# FXIMU.net
KiCad netlist of a schematic drawn in EAGLE
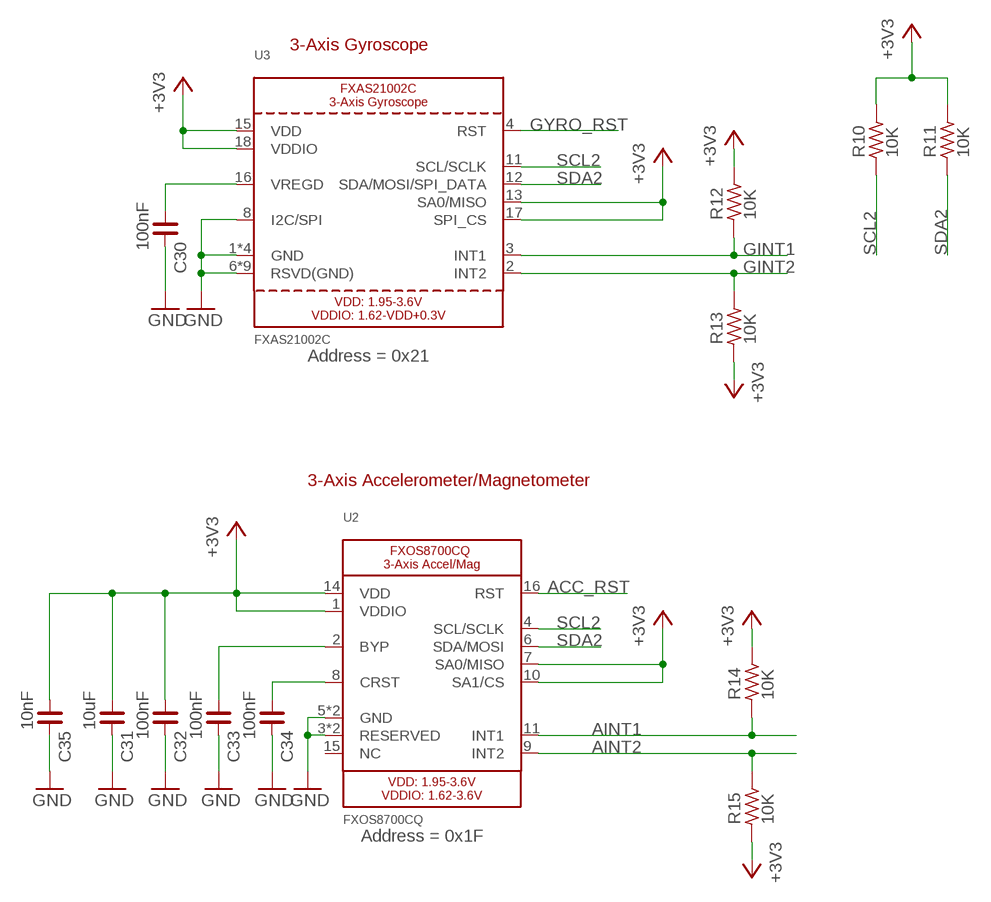
[diagram p0: schematic, sheet 1]
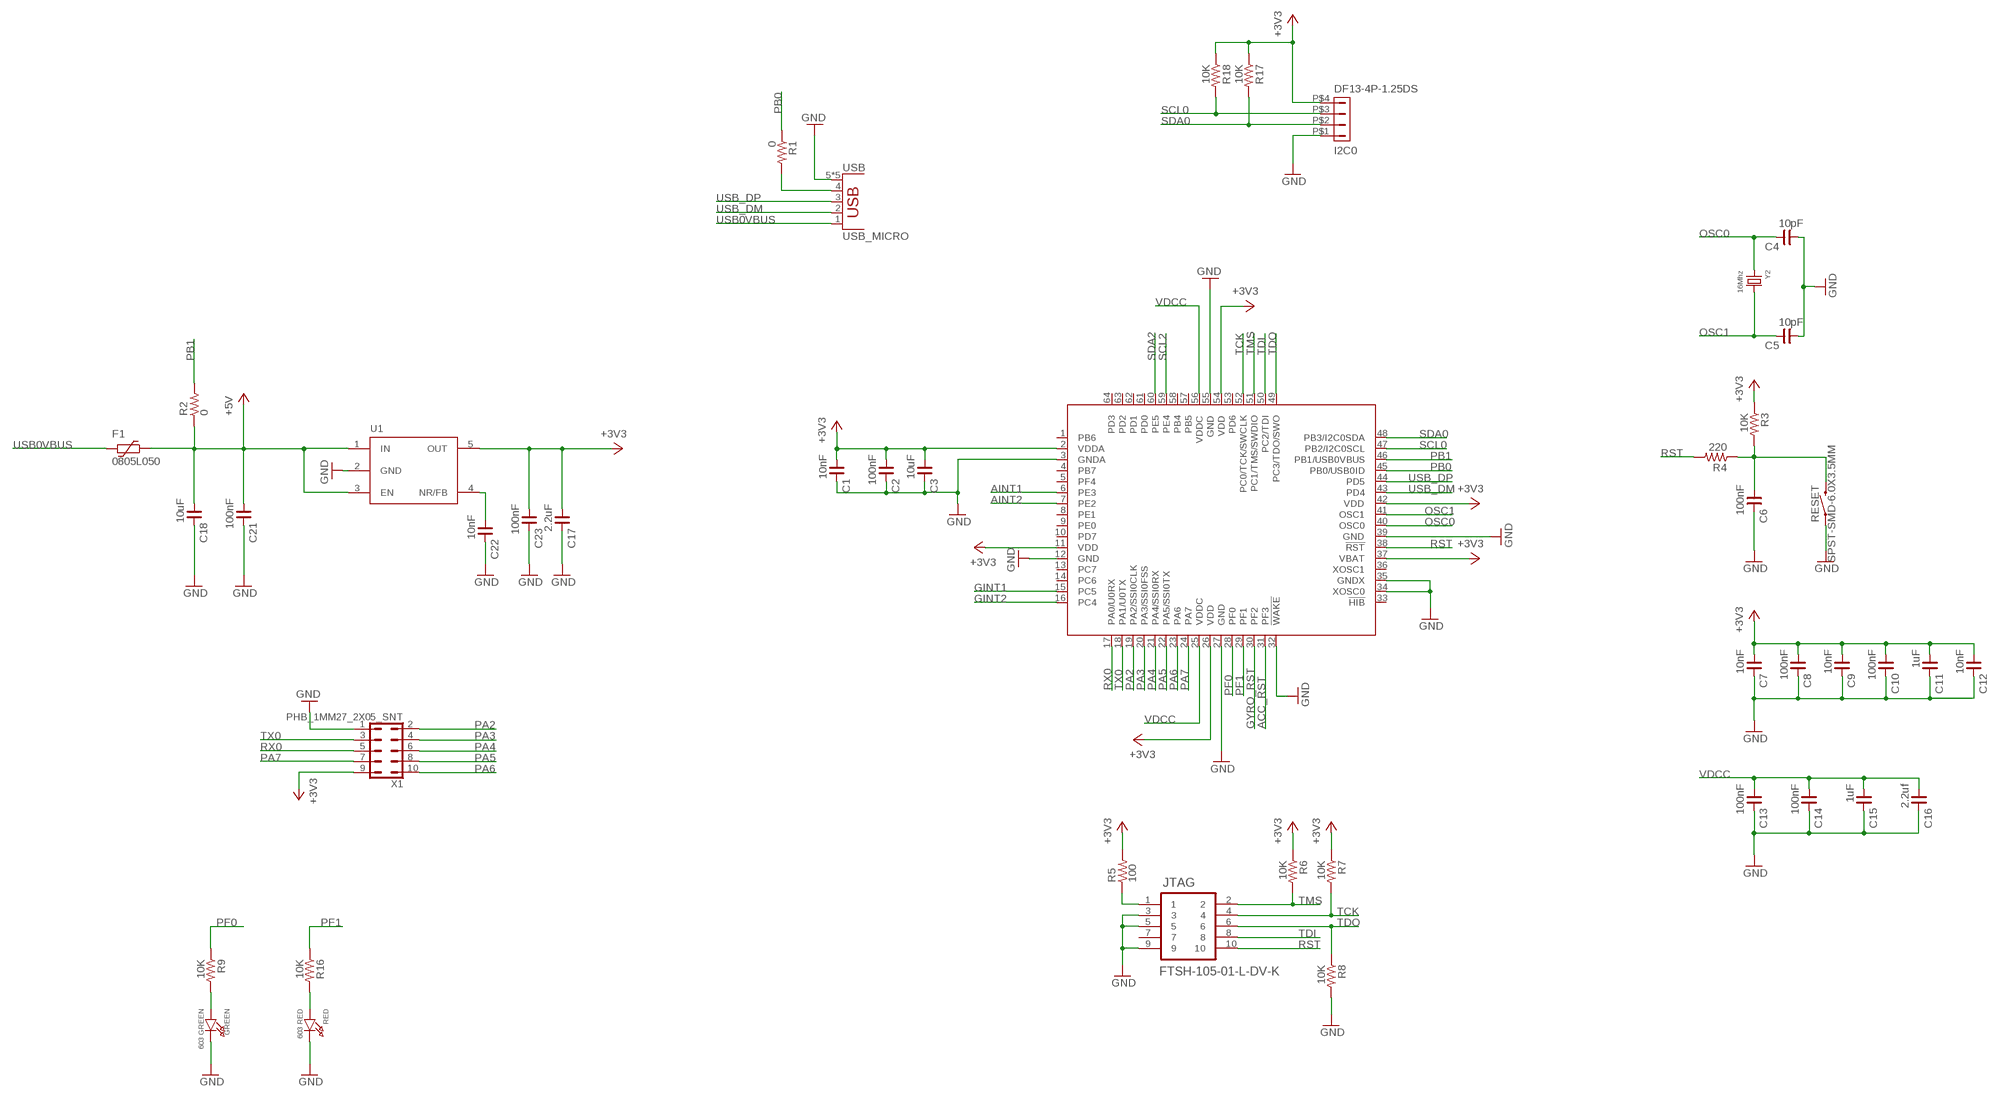
[diagram p1: schematic, sheet 2]

(export (version "E")
  (design (tool "Eeschema 10.0.6"))
  (components
    (comp (ref "C1")
      (value "10nF")
      (footprint "eagle-import:C0402")
      (libsource (lib "eagle-import") (part "C_0402"))
    )
    (comp (ref "C2")
      (value "100nF")
      (footprint "eagle-import:C0402")
      (libsource (lib "eagle-import") (part "C_0402"))
    )
    (comp (ref "C3")
      (value "10uF")
      (footprint "eagle-import:C0603")
      (libsource (lib "eagle-import") (part "C_0603"))
    )
    (comp (ref "C4")
      (value "10pF")
      (footprint "eagle-import:C0402")
      (libsource (lib "eagle-import") (part "C_0402"))
    )
    (comp (ref "C5")
      (value "10pF")
      (footprint "eagle-import:C0402")
      (libsource (lib "eagle-import") (part "C_0402"))
    )
    (comp (ref "C6")
      (value "100nF")
      (footprint "eagle-import:C0402")
      (libsource (lib "eagle-import") (part "C_0402"))
    )
    (comp (ref "C7")
      (value "10nF")
      (footprint "eagle-import:C0402")
      (libsource (lib "eagle-import") (part "C_0402"))
    )
    (comp (ref "C8")
      (value "100nF")
      (footprint "eagle-import:C0402")
      (libsource (lib "eagle-import") (part "C_0402"))
    )
    (comp (ref "C9")
      (value "10nF")
      (footprint "eagle-import:C0402")
      (libsource (lib "eagle-import") (part "C_0402"))
    )
    (comp (ref "C10")
      (value "100nF")
      (footprint "eagle-import:C0402")
      (libsource (lib "eagle-import") (part "C_0402"))
    )
    (comp (ref "C11")
      (value "1uF")
      (footprint "eagle-import:C0402")
      (libsource (lib "eagle-import") (part "C_0402"))
    )
    (comp (ref "C12")
      (value "10nF")
      (footprint "eagle-import:C0402")
      (libsource (lib "eagle-import") (part "C_0402"))
    )
    (comp (ref "C13")
      (value "100nF")
      (footprint "eagle-import:C0402")
      (libsource (lib "eagle-import") (part "C_0402"))
    )
    (comp (ref "C14")
      (value "100nF")
      (footprint "eagle-import:C0402")
      (libsource (lib "eagle-import") (part "C_0402"))
    )
    (comp (ref "C15")
      (value "1uF")
      (footprint "eagle-import:C0402")
      (libsource (lib "eagle-import") (part "C_0402"))
    )
    (comp (ref "C16")
      (value "2.2uf")
      (footprint "eagle-import:C0603")
      (libsource (lib "eagle-import") (part "C_0603"))
    )
    (comp (ref "C17")
      (value "2.2uF")
      (footprint "eagle-import:C0603")
      (libsource (lib "eagle-import") (part "C_0603"))
    )
    (comp (ref "C18")
      (value "10uF")
      (footprint "eagle-import:C0603")
      (libsource (lib "eagle-import") (part "C_0603"))
    )
    (comp (ref "C21")
      (value "100nF")
      (footprint "eagle-import:C0402")
      (libsource (lib "eagle-import") (part "C_0402"))
    )
    (comp (ref "C22")
      (value "10nF")
      (footprint "eagle-import:C0402")
      (libsource (lib "eagle-import") (part "C_0402"))
    )
    (comp (ref "C23")
      (value "100nF")
      (footprint "eagle-import:C0402")
      (libsource (lib "eagle-import") (part "C_0402"))
    )
    (comp (ref "F1")
      (value "0805L050")
      (footprint "eagle-import:0805L")
      (fields (field (name "MF") "Littelfuse"))
      (libsource (lib "eagle-import") (part "?0805L050"))
    )
    (comp (ref "GREEN")
      (value "603 GREEN")
      (footprint "eagle-import:CHIPLED_0603")
      (libsource (lib "eagle-import") (part "LED0603"))
    )
    (comp (ref "I2C0")
      (value "DF13-4P-1.25DS")
      (footprint "eagle-import:DF13-4P-1.25DS")
      (libsource (lib "eagle-import") (part "DF13-4P-1.25DS"))
    )
    (comp (ref "IC1")
      (value "TM4C123[7,G]XXPM")
      (footprint "eagle-import:PM_S-PQFP-G64")
      (libsource (lib "eagle-import") (part "TM4C123[7,G]XXPM"))
    )
    (comp (ref "JTAG")
      (value "FTSH-105-01-L-DV-K")
      (footprint "eagle-import:SAMTEC_FTSH-105-01-L-DV-K")
      (fields (field (name "MF") "Samtec"))
      (libsource (lib "eagle-import") (part "FTSH-105-01-L-DV-K"))
    )
    (comp (ref "R1")
      (value "0")
      (footprint "eagle-import:R0402")
      (libsource (lib "eagle-import") (part "R_0402"))
    )
    (comp (ref "R2")
      (value "0")
      (footprint "eagle-import:R0402")
      (libsource (lib "eagle-import") (part "R_0402"))
    )
    (comp (ref "R3")
      (value "10K")
      (footprint "eagle-import:R0402")
      (libsource (lib "eagle-import") (part "R_0402"))
    )
    (comp (ref "R4")
      (value "220")
      (footprint "eagle-import:R0402")
      (libsource (lib "eagle-import") (part "R_0402"))
    )
    (comp (ref "R5")
      (value "100")
      (footprint "eagle-import:R0402")
      (libsource (lib "eagle-import") (part "R_0402"))
    )
    (comp (ref "R6")
      (value "10K")
      (footprint "eagle-import:R0402")
      (libsource (lib "eagle-import") (part "R_0402"))
    )
    (comp (ref "R7")
      (value "10K")
      (footprint "eagle-import:R0402")
      (libsource (lib "eagle-import") (part "R_0402"))
    )
    (comp (ref "R8")
      (value "10K")
      (footprint "eagle-import:R0402")
      (libsource (lib "eagle-import") (part "R_0402"))
    )
    (comp (ref "R9")
      (value "10K")
      (footprint "eagle-import:R0402")
      (libsource (lib "eagle-import") (part "R_0402"))
    )
    (comp (ref "R16")
      (value "10K")
      (footprint "eagle-import:R0402")
      (libsource (lib "eagle-import") (part "R_0402"))
    )
    (comp (ref "R17")
      (value "10K")
      (footprint "eagle-import:R0402")
      (libsource (lib "eagle-import") (part "R_0402"))
    )
    (comp (ref "R18")
      (value "10K")
      (footprint "eagle-import:R0402")
      (libsource (lib "eagle-import") (part "R_0402"))
    )
    (comp (ref "RED")
      (value "603 RED")
      (footprint "eagle-import:CHIPLED_0603")
      (libsource (lib "eagle-import") (part "LED0603"))
    )
    (comp (ref "RESET")
      (value "SPST-SMD-6.0X3.5MM")
      (footprint "eagle-import:TACTILE_SWITCH_SMD_6.0X3.5MM")
      (libsource (lib "eagle-import") (part "MOMENTARY-SWITCH-SPST-SMD-6.0X3.5MM"))
    )
    (comp (ref "U1")
      (value "TPS73633")
      (footprint "eagle-import:SOT23-5L")
      (libsource (lib "eagle-import") (part "TPS73633"))
    )
    (comp (ref "USB")
      (value "USB_MICRO")
      (footprint "eagle-import:USB_MICRO_MOLEX_FULL")
      (libsource (lib "eagle-import") (part "USB_MICRO"))
    )
    (comp (ref "X1")
      (value "PHB_1MM27_2X05_SNT")
      (footprint "eagle-import:PHB_1MM27_2X05_SNT")
      (libsource (lib "eagle-import") (part "PHB_1MM27_2X05_SNT"))
    )
    (comp (ref "Y2")
      (value "16Mhz")
      (footprint "eagle-import:6X3.3MM")
      (libsource (lib "eagle-import") (part "CRYSTAL.6X3.3MM"))
    )
    (comp (ref "C30")
      (value "100nF")
      (footprint "eagle-import:C0402")
      (libsource (lib "eagle-import") (part "C_0402"))
    )
    (comp (ref "C31")
      (value "10uF")
      (footprint "eagle-import:C0603")
      (libsource (lib "eagle-import") (part "C_0603"))
    )
    (comp (ref "C32")
      (value "100nF")
      (footprint "eagle-import:C0402")
      (libsource (lib "eagle-import") (part "C_0402"))
    )
    (comp (ref "C33")
      (value "100nF")
      (footprint "eagle-import:C0402")
      (libsource (lib "eagle-import") (part "C_0402"))
    )
    (comp (ref "C34")
      (value "100nF")
      (footprint "eagle-import:C0402")
      (libsource (lib "eagle-import") (part "C_0402"))
    )
    (comp (ref "C35")
      (value "10nF")
      (footprint "eagle-import:C0402")
      (libsource (lib "eagle-import") (part "C_0402"))
    )
    (comp (ref "R10")
      (value "10K")
      (footprint "eagle-import:R0402")
      (libsource (lib "eagle-import") (part "R_0402"))
    )
    (comp (ref "R11")
      (value "10K")
      (footprint "eagle-import:R0402")
      (libsource (lib "eagle-import") (part "R_0402"))
    )
    (comp (ref "R12")
      (value "10K")
      (footprint "eagle-import:R0402")
      (libsource (lib "eagle-import") (part "R_0402"))
    )
    (comp (ref "R13")
      (value "10K")
      (footprint "eagle-import:R0402")
      (libsource (lib "eagle-import") (part "R_0402"))
    )
    (comp (ref "R14")
      (value "10K")
      (footprint "eagle-import:R0402")
      (libsource (lib "eagle-import") (part "R_0402"))
    )
    (comp (ref "R15")
      (value "10K")
      (footprint "eagle-import:R0402")
      (libsource (lib "eagle-import") (part "R_0402"))
    )
    (comp (ref "U2")
      (value "FXOS8700CQ")
      (footprint "eagle-import:QFN16_3MM_FREESCALE_5X3")
      (libsource (lib "eagle-import") (part "ACCEL_MAG_FXOS8700CQ"))
    )
    (comp (ref "U3")
      (value "FXAS21002C")
      (footprint "eagle-import:QFN24_4MM_FREESCALE_7X5")
      (libsource (lib "eagle-import") (part "GYRO_FXAS21002C"))
    )
  )
  (nets
    (net (code "1") (name "+3V3") (class "Default")
      (node (ref "C1") (pin "1") (pinfunction "1_1") (pintype "passive"))
      (node (ref "C10") (pin "1") (pinfunction "1_1") (pintype "passive"))
      (node (ref "C11") (pin "1") (pinfunction "1_1") (pintype "passive"))
      (node (ref "C12") (pin "1") (pinfunction "1_1") (pintype "passive"))
      (node (ref "C17") (pin "1") (pinfunction "1_1") (pintype "passive"))
      (node (ref "C2") (pin "1") (pinfunction "1_1") (pintype "passive"))
      (node (ref "C23") (pin "1") (pinfunction "1_1") (pintype "passive"))
      (node (ref "C3") (pin "1") (pinfunction "1_1") (pintype "passive"))
      (node (ref "C31") (pin "1") (pinfunction "1_1") (pintype "passive"))
      (node (ref "C32") (pin "1") (pinfunction "1_1") (pintype "passive"))
      (node (ref "C35") (pin "1") (pinfunction "1_1") (pintype "passive"))
      (node (ref "C7") (pin "1") (pinfunction "1_1") (pintype "passive"))
      (node (ref "C8") (pin "1") (pinfunction "1_1") (pintype "passive"))
      (node (ref "C9") (pin "1") (pinfunction "1_1") (pintype "passive"))
      (node (ref "I2C0") (pin "P$4") (pinfunction "4_P$4") (pintype "passive"))
      (node (ref "IC1") (pin "11") (pinfunction "VDD_11") (pintype "bidirectional"))
      (node (ref "IC1") (pin "2") (pinfunction "VDDA_2") (pintype "bidirectional"))
      (node (ref "IC1") (pin "26") (pinfunction "VDD_26") (pintype "bidirectional"))
      (node (ref "IC1") (pin "37") (pinfunction "VBAT_37") (pintype "bidirectional"))
      (node (ref "IC1") (pin "42") (pinfunction "VDD_42") (pintype "bidirectional"))
      (node (ref "IC1") (pin "54") (pinfunction "VDD_54") (pintype "bidirectional"))
      (node (ref "R10") (pin "2") (pinfunction "2_2") (pintype "passive"))
      (node (ref "R11") (pin "2") (pinfunction "2_2") (pintype "passive"))
      (node (ref "R12") (pin "2") (pinfunction "2_2") (pintype "passive"))
      (node (ref "R13") (pin "1") (pinfunction "1_1") (pintype "passive"))
      (node (ref "R14") (pin "2") (pinfunction "2_2") (pintype "passive"))
      (node (ref "R15") (pin "1") (pinfunction "1_1") (pintype "passive"))
      (node (ref "R17") (pin "1") (pinfunction "1_1") (pintype "passive"))
      (node (ref "R18") (pin "1") (pinfunction "1_1") (pintype "passive"))
      (node (ref "R3") (pin "1") (pinfunction "1_1") (pintype "passive"))
      (node (ref "R5") (pin "2") (pinfunction "2_2") (pintype "passive"))
      (node (ref "R6") (pin "1") (pinfunction "1_1") (pintype "passive"))
      (node (ref "R7") (pin "1") (pinfunction "1_1") (pintype "passive"))
      (node (ref "U1") (pin "5") (pinfunction "OUT_5") (pintype "bidirectional"))
      (node (ref "U2") (pin "1") (pinfunction "VDDIO_1") (pintype "bidirectional"))
      (node (ref "U2") (pin "10") (pinfunction "SA1/CS_10") (pintype "bidirectional"))
      (node (ref "U2") (pin "14") (pinfunction "VDD_14") (pintype "bidirectional"))
      (node (ref "U2") (pin "7") (pinfunction "SA0/MISO_7") (pintype "bidirectional"))
      (node (ref "U3") (pin "13") (pinfunction "SA0/MISO_13") (pintype "bidirectional"))
      (node (ref "U3") (pin "15") (pinfunction "VDD_15") (pintype "bidirectional"))
      (node (ref "U3") (pin "17") (pinfunction "SPI_CS_17") (pintype "bidirectional"))
      (node (ref "U3") (pin "18") (pinfunction "VDDIO_18") (pintype "bidirectional"))
      (node (ref "X1") (pin "9") (pinfunction "9_9") (pintype "passive"))
    )
    (net (code "2") (name "+5V") (class "Default")
      (node (ref "C18") (pin "1") (pinfunction "1_1") (pintype "passive"))
      (node (ref "C21") (pin "1") (pinfunction "1_1") (pintype "passive"))
      (node (ref "F1") (pin "1") (pinfunction "1_1") (pintype "passive"))
      (node (ref "R2") (pin "1") (pinfunction "1_1") (pintype "passive"))
      (node (ref "U1") (pin "1") (pinfunction "IN_1") (pintype "bidirectional"))
      (node (ref "U1") (pin "3") (pinfunction "EN_3") (pintype "bidirectional"))
    )
    (net (code "3") (name "ACC_RST") (class "Default")
      (node (ref "IC1") (pin "31") (pinfunction "PF3_31") (pintype "bidirectional"))
      (node (ref "U2") (pin "16") (pinfunction "RST_16") (pintype "bidirectional"))
    )
    (net (code "4") (name "AINT1") (class "Default")
      (node (ref "IC1") (pin "6") (pinfunction "PE3_6") (pintype "bidirectional"))
      (node (ref "R14") (pin "1") (pinfunction "1_1") (pintype "passive"))
      (node (ref "U2") (pin "11") (pinfunction "INT1_11") (pintype "bidirectional"))
    )
    (net (code "5") (name "AINT2") (class "Default")
      (node (ref "IC1") (pin "7") (pinfunction "PE2_7") (pintype "bidirectional"))
      (node (ref "R15") (pin "2") (pinfunction "2_2") (pintype "passive"))
      (node (ref "U2") (pin "9") (pinfunction "INT2_9") (pintype "bidirectional"))
    )
    (net (code "6") (name "GINT1") (class "Default")
      (node (ref "IC1") (pin "15") (pinfunction "PC5_15") (pintype "bidirectional"))
      (node (ref "R12") (pin "1") (pinfunction "1_1") (pintype "passive"))
      (node (ref "U3") (pin "3") (pinfunction "INT1_3") (pintype "bidirectional"))
    )
    (net (code "7") (name "GINT2") (class "Default")
      (node (ref "IC1") (pin "16") (pinfunction "PC4_16") (pintype "bidirectional"))
      (node (ref "R13") (pin "2") (pinfunction "2_2") (pintype "passive"))
      (node (ref "U3") (pin "2") (pinfunction "INT2_2") (pintype "bidirectional"))
    )
    (net (code "8") (name "GND") (class "Default")
      (node (ref "C1") (pin "2") (pinfunction "2_2") (pintype "passive"))
      (node (ref "C10") (pin "2") (pinfunction "2_2") (pintype "passive"))
      (node (ref "C11") (pin "2") (pinfunction "2_2") (pintype "passive"))
      (node (ref "C12") (pin "2") (pinfunction "2_2") (pintype "passive"))
      (node (ref "C13") (pin "2") (pinfunction "2_2") (pintype "passive"))
      (node (ref "C14") (pin "2") (pinfunction "2_2") (pintype "passive"))
      (node (ref "C15") (pin "2") (pinfunction "2_2") (pintype "passive"))
      (node (ref "C16") (pin "2") (pinfunction "2_2") (pintype "passive"))
      (node (ref "C17") (pin "2") (pinfunction "2_2") (pintype "passive"))
      (node (ref "C18") (pin "2") (pinfunction "2_2") (pintype "passive"))
      (node (ref "C2") (pin "2") (pinfunction "2_2") (pintype "passive"))
      (node (ref "C21") (pin "2") (pinfunction "2_2") (pintype "passive"))
      (node (ref "C22") (pin "2") (pinfunction "2_2") (pintype "passive"))
      (node (ref "C23") (pin "2") (pinfunction "2_2") (pintype "passive"))
      (node (ref "C3") (pin "2") (pinfunction "2_2") (pintype "passive"))
      (node (ref "C30") (pin "2") (pinfunction "2_2") (pintype "passive"))
      (node (ref "C31") (pin "2") (pinfunction "2_2") (pintype "passive"))
      (node (ref "C32") (pin "2") (pinfunction "2_2") (pintype "passive"))
      (node (ref "C33") (pin "2") (pinfunction "2_2") (pintype "passive"))
      (node (ref "C34") (pin "2") (pinfunction "2_2") (pintype "passive"))
      (node (ref "C35") (pin "2") (pinfunction "2_2") (pintype "passive"))
      (node (ref "C4") (pin "1") (pinfunction "1_1") (pintype "passive"))
      (node (ref "C5") (pin "1") (pinfunction "1_1") (pintype "passive"))
      (node (ref "C6") (pin "2") (pinfunction "2_2") (pintype "passive"))
      (node (ref "C7") (pin "2") (pinfunction "2_2") (pintype "passive"))
      (node (ref "C8") (pin "2") (pinfunction "2_2") (pintype "passive"))
      (node (ref "C9") (pin "2") (pinfunction "2_2") (pintype "passive"))
      (node (ref "GREEN") (pin "C") (pinfunction "C_C") (pintype "passive"))
      (node (ref "I2C0") (pin "P$1") (pinfunction "1_P$1") (pintype "passive"))
      (node (ref "IC1") (pin "12") (pinfunction "GND_12") (pintype "bidirectional"))
      (node (ref "IC1") (pin "27") (pinfunction "GND_27") (pintype "bidirectional"))
      (node (ref "IC1") (pin "3") (pinfunction "GNDA_3") (pintype "bidirectional"))
      (node (ref "IC1") (pin "32") (pinfunction "~{WAKE}_32") (pintype "bidirectional"))
      (node (ref "IC1") (pin "34") (pinfunction "XOSC0_34") (pintype "bidirectional"))
      (node (ref "IC1") (pin "35") (pinfunction "GNDX_35") (pintype "bidirectional"))
      (node (ref "IC1") (pin "39") (pinfunction "GND_39") (pintype "bidirectional"))
      (node (ref "IC1") (pin "55") (pinfunction "GND_55") (pintype "bidirectional"))
      (node (ref "JTAG") (pin "3") (pinfunction "3_3") (pintype "passive"))
      (node (ref "JTAG") (pin "5") (pinfunction "5_5") (pintype "passive"))
      (node (ref "JTAG") (pin "9") (pinfunction "9_9") (pintype "passive"))
      (node (ref "R8") (pin "2") (pinfunction "2_2") (pintype "passive"))
      (node (ref "RED") (pin "C") (pinfunction "C_C") (pintype "passive"))
      (node (ref "RESET") (pin "1") (pinfunction "1_1") (pintype "passive"))
      (node (ref "U1") (pin "2") (pinfunction "GND_2") (pintype "bidirectional"))
      (node (ref "U2") (pin "12") (pinfunction "GND_12") (pintype "bidirectional"))
      (node (ref "U2") (pin "13") (pinfunction "RESERVED_13") (pintype "bidirectional"))
      (node (ref "U2") (pin "3") (pinfunction "RESERVED_3") (pintype "bidirectional"))
      (node (ref "U2") (pin "5") (pinfunction "GND_5") (pintype "bidirectional"))
      (node (ref "U3") (pin "1") (pinfunction "GND_1") (pintype "bidirectional"))
      (node (ref "U3") (pin "10") (pinfunction "RSVD(GND)_10") (pintype "bidirectional"))
      (node (ref "U3") (pin "14") (pinfunction "GND_14") (pintype "bidirectional"))
      (node (ref "U3") (pin "19") (pinfunction "GND_19") (pintype "bidirectional"))
      (node (ref "U3") (pin "20") (pinfunction "RSVD(GND)_20") (pintype "bidirectional"))
      (node (ref "U3") (pin "21") (pinfunction "RSVD(GND)_21") (pintype "bidirectional"))
      (node (ref "U3") (pin "22") (pinfunction "RSVD(GND)_22") (pintype "bidirectional"))
      (node (ref "U3") (pin "23") (pinfunction "RSVD(GND)_23") (pintype "bidirectional"))
      (node (ref "U3") (pin "24") (pinfunction "RSVD(GND)_24") (pintype "bidirectional"))
      (node (ref "U3") (pin "5") (pinfunction "GND_5") (pintype "bidirectional"))
      (node (ref "U3") (pin "6") (pinfunction "RSVD(GND)_6") (pintype "bidirectional"))
      (node (ref "U3") (pin "7") (pinfunction "RSVD(GND)_7") (pintype "bidirectional"))
      (node (ref "U3") (pin "8") (pinfunction "I2C/SPI_8") (pintype "bidirectional"))
      (node (ref "U3") (pin "9") (pinfunction "RSVD(GND)_9") (pintype "bidirectional"))
      (node (ref "USB") (pin "5") (pinfunction "GND_5") (pintype "bidirectional"))
      (node (ref "USB") (pin "P$1") (pinfunction "GND_P$1") (pintype "bidirectional"))
      (node (ref "USB") (pin "P$2") (pinfunction "GND_P$2") (pintype "bidirectional"))
      (node (ref "USB") (pin "P$3") (pinfunction "GND_P$3") (pintype "bidirectional"))
      (node (ref "USB") (pin "P$4") (pinfunction "GND_P$4") (pintype "bidirectional"))
      (node (ref "X1") (pin "1") (pinfunction "1_1") (pintype "passive"))
    )
    (net (code "9") (name "GYRO_RST") (class "Default")
      (node (ref "IC1") (pin "30") (pinfunction "PF2_30") (pintype "bidirectional"))
      (node (ref "U3") (pin "4") (pinfunction "RST_4") (pintype "bidirectional"))
    )
    (net (code "10") (name "Net-(C6-Pad1)") (class "Default")
      (node (ref "C6") (pin "1") (pinfunction "1_1") (pintype "passive"))
      (node (ref "R3") (pin "2") (pinfunction "2_2") (pintype "passive"))
      (node (ref "R4") (pin "1") (pinfunction "1_1") (pintype "passive"))
      (node (ref "RESET") (pin "2") (pinfunction "2_2") (pintype "passive"))
    )
    (net (code "11") (name "Net-(GREEN-PadA)") (class "Default")
      (node (ref "GREEN") (pin "A") (pinfunction "A_A") (pintype "passive"))
      (node (ref "R9") (pin "2") (pinfunction "2_2") (pintype "passive"))
    )
    (net (code "12") (name "Net-(JTAG-Pad1)") (class "Default")
      (node (ref "JTAG") (pin "1") (pinfunction "1_1") (pintype "passive"))
      (node (ref "R5") (pin "1") (pinfunction "1_1") (pintype "passive"))
    )
    (net (code "13") (name "Net-(R16-Pad2)") (class "Default")
      (node (ref "R16") (pin "2") (pinfunction "2_2") (pintype "passive"))
      (node (ref "RED") (pin "A") (pinfunction "A_A") (pintype "passive"))
    )
    (net (code "14") (name "Net-(U1-NR{slash}FB)") (class "Default")
      (node (ref "C22") (pin "1") (pinfunction "1_1") (pintype "passive"))
      (node (ref "U1") (pin "4") (pinfunction "NR/FB_4") (pintype "bidirectional"))
    )
    (net (code "15") (name "Net-(U2-BYP)") (class "Default")
      (node (ref "C33") (pin "1") (pinfunction "1_1") (pintype "passive"))
      (node (ref "U2") (pin "2") (pinfunction "BYP_2") (pintype "bidirectional"))
    )
    (net (code "16") (name "Net-(U2-CRST)") (class "Default")
      (node (ref "C34") (pin "1") (pinfunction "1_1") (pintype "passive"))
      (node (ref "U2") (pin "8") (pinfunction "CRST_8") (pintype "bidirectional"))
    )
    (net (code "17") (name "Net-(U3-VREGD)") (class "Default")
      (node (ref "C30") (pin "1") (pinfunction "1_1") (pintype "passive"))
      (node (ref "U3") (pin "16") (pinfunction "VREGD_16") (pintype "bidirectional"))
    )
    (net (code "18") (name "Net-(USB-ID)") (class "Default")
      (node (ref "R1") (pin "2") (pinfunction "2_2") (pintype "passive"))
      (node (ref "USB") (pin "4") (pinfunction "ID_4") (pintype "bidirectional"))
    )
    (net (code "19") (name "OSC0") (class "Default")
      (node (ref "C4") (pin "2") (pinfunction "2_2") (pintype "passive"))
      (node (ref "IC1") (pin "40") (pinfunction "OSC0_40") (pintype "bidirectional"))
      (node (ref "Y2") (pin "1") (pinfunction "1_1") (pintype "passive"))
    )
    (net (code "20") (name "OSC1") (class "Default")
      (node (ref "C5") (pin "2") (pinfunction "2_2") (pintype "passive"))
      (node (ref "IC1") (pin "41") (pinfunction "OSC1_41") (pintype "bidirectional"))
      (node (ref "Y2") (pin "2") (pinfunction "2_2") (pintype "passive"))
    )
    (net (code "21") (name "PA2") (class "Default")
      (node (ref "IC1") (pin "19") (pinfunction "PA2/SSI0CLK_19") (pintype "bidirectional"))
      (node (ref "X1") (pin "2") (pinfunction "2_2") (pintype "passive"))
    )
    (net (code "22") (name "PA3") (class "Default")
      (node (ref "IC1") (pin "20") (pinfunction "PA3/SSI0FSS_20") (pintype "bidirectional"))
      (node (ref "X1") (pin "4") (pinfunction "4_4") (pintype "passive"))
    )
    (net (code "23") (name "PA4") (class "Default")
      (node (ref "IC1") (pin "21") (pinfunction "PA4/SSI0RX_21") (pintype "bidirectional"))
      (node (ref "X1") (pin "6") (pinfunction "6_6") (pintype "passive"))
    )
    (net (code "24") (name "PA5") (class "Default")
      (node (ref "IC1") (pin "22") (pinfunction "PA5/SSI0TX_22") (pintype "bidirectional"))
      (node (ref "X1") (pin "8") (pinfunction "8_8") (pintype "passive"))
    )
    (net (code "25") (name "PA6") (class "Default")
      (node (ref "IC1") (pin "23") (pinfunction "PA6_23") (pintype "bidirectional"))
      (node (ref "X1") (pin "10") (pinfunction "10_10") (pintype "passive"))
    )
    (net (code "26") (name "PA7") (class "Default")
      (node (ref "IC1") (pin "24") (pinfunction "PA7_24") (pintype "bidirectional"))
      (node (ref "X1") (pin "7") (pinfunction "7_7") (pintype "passive"))
    )
    (net (code "27") (name "PB0") (class "Default")
      (node (ref "IC1") (pin "45") (pinfunction "PB0/USB0ID_45") (pintype "bidirectional"))
      (node (ref "R1") (pin "1") (pinfunction "1_1") (pintype "passive"))
    )
    (net (code "28") (name "PB1") (class "Default")
      (node (ref "IC1") (pin "46") (pinfunction "PB1/USB0VBUS_46") (pintype "bidirectional"))
      (node (ref "R2") (pin "2") (pinfunction "2_2") (pintype "passive"))
    )
    (net (code "29") (name "PF0") (class "Default")
      (node (ref "IC1") (pin "28") (pinfunction "PF0_28") (pintype "bidirectional"))
      (node (ref "R9") (pin "1") (pinfunction "1_1") (pintype "passive"))
    )
    (net (code "30") (name "PF1") (class "Default")
      (node (ref "IC1") (pin "29") (pinfunction "PF1_29") (pintype "bidirectional"))
      (node (ref "R16") (pin "1") (pinfunction "1_1") (pintype "passive"))
    )
    (net (code "31") (name "RST") (class "Default")
      (node (ref "IC1") (pin "38") (pinfunction "~{RST}_38") (pintype "bidirectional"))
      (node (ref "JTAG") (pin "10") (pinfunction "10_10") (pintype "passive"))
      (node (ref "R4") (pin "2") (pinfunction "2_2") (pintype "passive"))
    )
    (net (code "32") (name "RX0") (class "Default")
      (node (ref "IC1") (pin "17") (pinfunction "PA0/U0RX_17") (pintype "bidirectional"))
      (node (ref "X1") (pin "5") (pinfunction "5_5") (pintype "passive"))
    )
    (net (code "33") (name "SCL0") (class "Default")
      (node (ref "I2C0") (pin "P$3") (pinfunction "3_P$3") (pintype "passive"))
      (node (ref "IC1") (pin "47") (pinfunction "PB2/I2C0SCL_47") (pintype "bidirectional"))
      (node (ref "R18") (pin "2") (pinfunction "2_2") (pintype "passive"))
    )
    (net (code "34") (name "SCL2") (class "Default")
      (node (ref "IC1") (pin "59") (pinfunction "PE4_59") (pintype "bidirectional"))
      (node (ref "R10") (pin "1") (pinfunction "1_1") (pintype "passive"))
      (node (ref "U2") (pin "4") (pinfunction "SCL/SCLK_4") (pintype "bidirectional"))
      (node (ref "U3") (pin "11") (pinfunction "SCL/SCLK_11") (pintype "bidirectional"))
    )
    (net (code "35") (name "SDA0") (class "Default")
      (node (ref "I2C0") (pin "P$2") (pinfunction "2_P$2") (pintype "passive"))
      (node (ref "IC1") (pin "48") (pinfunction "PB3/I2C0SDA_48") (pintype "bidirectional"))
      (node (ref "R17") (pin "2") (pinfunction "2_2") (pintype "passive"))
    )
    (net (code "36") (name "SDA2") (class "Default")
      (node (ref "IC1") (pin "60") (pinfunction "PE5_60") (pintype "bidirectional"))
      (node (ref "R11") (pin "1") (pinfunction "1_1") (pintype "passive"))
      (node (ref "U2") (pin "6") (pinfunction "SDA/MOSI_6") (pintype "bidirectional"))
      (node (ref "U3") (pin "12") (pinfunction "SDA/MOSI/SPI_DATA_12") (pintype "bidirectional"))
    )
    (net (code "37") (name "TCK") (class "Default")
      (node (ref "IC1") (pin "52") (pinfunction "PC0/TCK/SWCLK_52") (pintype "bidirectional"))
      (node (ref "JTAG") (pin "4") (pinfunction "4_4") (pintype "passive"))
      (node (ref "R7") (pin "2") (pinfunction "2_2") (pintype "passive"))
    )
    (net (code "38") (name "TDI") (class "Default")
      (node (ref "IC1") (pin "50") (pinfunction "PC2/TDI_50") (pintype "bidirectional"))
      (node (ref "JTAG") (pin "8") (pinfunction "8_8") (pintype "passive"))
    )
    (net (code "39") (name "TDO") (class "Default")
      (node (ref "IC1") (pin "49") (pinfunction "PC3/TDO/SWO_49") (pintype "bidirectional"))
      (node (ref "JTAG") (pin "6") (pinfunction "6_6") (pintype "passive"))
      (node (ref "R8") (pin "1") (pinfunction "1_1") (pintype "passive"))
    )
    (net (code "40") (name "TMS") (class "Default")
      (node (ref "IC1") (pin "51") (pinfunction "PC1/TMS/SWDIO_51") (pintype "bidirectional"))
      (node (ref "JTAG") (pin "2") (pinfunction "2_2") (pintype "passive"))
      (node (ref "R6") (pin "2") (pinfunction "2_2") (pintype "passive"))
    )
    (net (code "41") (name "TX0") (class "Default")
      (node (ref "IC1") (pin "18") (pinfunction "PA1/U0TX_18") (pintype "bidirectional"))
      (node (ref "X1") (pin "3") (pinfunction "3_3") (pintype "passive"))
    )
    (net (code "42") (name "USB0VBUS") (class "Default")
      (node (ref "F1") (pin "2") (pinfunction "2_2") (pintype "passive"))
      (node (ref "USB") (pin "1") (pinfunction "VBUS_1") (pintype "bidirectional"))
    )
    (net (code "43") (name "USB_DM") (class "Default")
      (node (ref "IC1") (pin "43") (pinfunction "PD4_43") (pintype "bidirectional"))
      (node (ref "USB") (pin "2") (pinfunction "D-_2") (pintype "bidirectional"))
    )
    (net (code "44") (name "USB_DP") (class "Default")
      (node (ref "IC1") (pin "44") (pinfunction "PD5_44") (pintype "bidirectional"))
      (node (ref "USB") (pin "3") (pinfunction "D+_3") (pintype "bidirectional"))
    )
    (net (code "45") (name "VDCC") (class "Default")
      (node (ref "C13") (pin "1") (pinfunction "1_1") (pintype "passive"))
      (node (ref "C14") (pin "1") (pinfunction "1_1") (pintype "passive"))
      (node (ref "C15") (pin "1") (pinfunction "1_1") (pintype "passive"))
      (node (ref "C16") (pin "1") (pinfunction "1_1") (pintype "passive"))
      (node (ref "IC1") (pin "25") (pinfunction "VDDC_25") (pintype "bidirectional"))
      (node (ref "IC1") (pin "56") (pinfunction "VDDC_56") (pintype "bidirectional"))
    )
    (net (code "46") (name "unconnected-(IC1-PB4-Pad58)") (class "Default")
      (node (ref "IC1") (pin "58") (pinfunction "PB4_58") (pintype "bidirectional"))
    )
    (net (code "47") (name "unconnected-(IC1-PB5-Pad57)") (class "Default")
      (node (ref "IC1") (pin "57") (pinfunction "PB5_57") (pintype "bidirectional"))
    )
    (net (code "48") (name "unconnected-(IC1-PB6-Pad1)") (class "Default")
      (node (ref "IC1") (pin "1") (pinfunction "PB6_1") (pintype "bidirectional"))
    )
    (net (code "49") (name "unconnected-(IC1-PB7-Pad4)") (class "Default")
      (node (ref "IC1") (pin "4") (pinfunction "PB7_4") (pintype "bidirectional"))
    )
    (net (code "50") (name "unconnected-(IC1-PC6-Pad14)") (class "Default")
      (node (ref "IC1") (pin "14") (pinfunction "PC6_14") (pintype "bidirectional"))
    )
    (net (code "51") (name "unconnected-(IC1-PC7-Pad13)") (class "Default")
      (node (ref "IC1") (pin "13") (pinfunction "PC7_13") (pintype "bidirectional"))
    )
    (net (code "52") (name "unconnected-(IC1-PD0-Pad61)") (class "Default")
      (node (ref "IC1") (pin "61") (pinfunction "PD0_61") (pintype "bidirectional"))
    )
    (net (code "53") (name "unconnected-(IC1-PD1-Pad62)") (class "Default")
      (node (ref "IC1") (pin "62") (pinfunction "PD1_62") (pintype "bidirectional"))
    )
    (net (code "54") (name "unconnected-(IC1-PD2-Pad63)") (class "Default")
      (node (ref "IC1") (pin "63") (pinfunction "PD2_63") (pintype "bidirectional"))
    )
    (net (code "55") (name "unconnected-(IC1-PD3-Pad64)") (class "Default")
      (node (ref "IC1") (pin "64") (pinfunction "PD3_64") (pintype "bidirectional"))
    )
    (net (code "56") (name "unconnected-(IC1-PD6-Pad53)") (class "Default")
      (node (ref "IC1") (pin "53") (pinfunction "PD6_53") (pintype "bidirectional"))
    )
    (net (code "57") (name "unconnected-(IC1-PD7-Pad10)") (class "Default")
      (node (ref "IC1") (pin "10") (pinfunction "PD7_10") (pintype "bidirectional"))
    )
    (net (code "58") (name "unconnected-(IC1-PE0-Pad9)") (class "Default")
      (node (ref "IC1") (pin "9") (pinfunction "PE0_9") (pintype "bidirectional"))
    )
    (net (code "59") (name "unconnected-(IC1-PE1-Pad8)") (class "Default")
      (node (ref "IC1") (pin "8") (pinfunction "PE1_8") (pintype "bidirectional"))
    )
    (net (code "60") (name "unconnected-(IC1-PF4-Pad5)") (class "Default")
      (node (ref "IC1") (pin "5") (pinfunction "PF4_5") (pintype "bidirectional"))
    )
    (net (code "61") (name "unconnected-(IC1-XOSC1-Pad36)") (class "Default")
      (node (ref "IC1") (pin "36") (pinfunction "XOSC1_36") (pintype "bidirectional"))
    )
    (net (code "62") (name "unconnected-(IC1-~{HIB}-Pad33)") (class "Default")
      (node (ref "IC1") (pin "33") (pinfunction "~{HIB}_33") (pintype "bidirectional"))
    )
    (net (code "63") (name "unconnected-(JTAG-Pad7)") (class "Default")
      (node (ref "JTAG") (pin "7") (pinfunction "7_7") (pintype "passive"))
    )
    (net (code "64") (name "unconnected-(U2-NC-Pad15)") (class "Default")
      (node (ref "U2") (pin "15") (pinfunction "NC_15") (pintype "bidirectional"))
    )
  )
)
